# Sheet1.net
KiCad netlist of a schematic drawn in Altium Designer
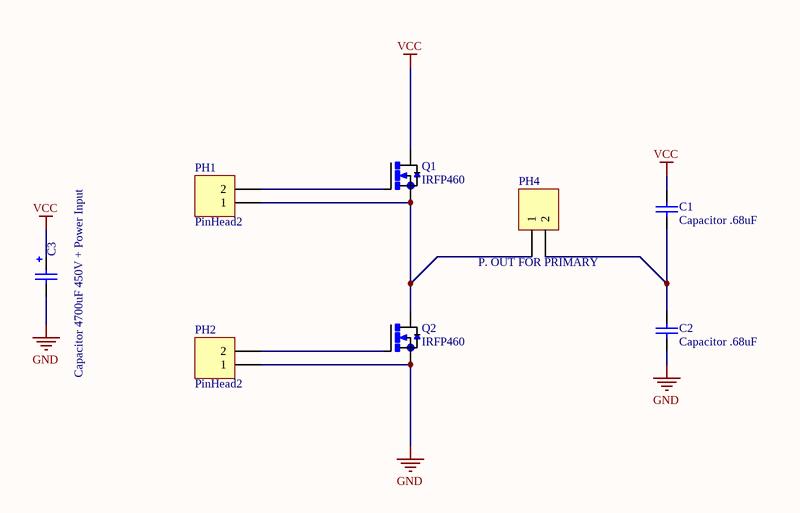
[diagram p0: Sheet1.SchDoc]

(export (version "E")
  (design (tool "Eeschema 10.0.6"))
  (components
    (comp (ref "C1")
      (value "Capacitor .68uF")
      (footprint "Capacitor .68uF")
      (libsource (lib "SPaivachlib1") (part "Capacitor .68uF"))
    )
    (comp (ref "C2")
      (value "Capacitor .68uF")
      (footprint "Capacitor .68uF")
      (libsource (lib "SPaivachlib1") (part "Capacitor .68uF"))
    )
    (comp (ref "C3")
      (value "Capacitor 4700uF 450V + Power Input")
      (footprint "Capacitor 4700uF 450V RIFA")
      (libsource (lib "SPaivachlib1") (part "Capacitor 4700uF 450V"))
    )
    (comp (ref "PH1")
      (value "PinHead2")
      (footprint "PinHead2")
      (libsource (lib "SPaivachlib1") (part "PinHead2"))
    )
    (comp (ref "PH2")
      (value "PinHead2")
      (footprint "PinHead2")
      (libsource (lib "SPaivachlib1") (part "PinHead2"))
    )
    (comp (ref "PH4")
      (value "P. OUT FOR PRIMARY")
      (footprint "P. OUT FOR PRIMARY")
      (libsource (lib "SPaivachlib1") (part "P. OUT FOR PRIMARY"))
    )
    (comp (ref "Q1")
      (value "IRFP460")
      (footprint "IRFP460")
      (libsource (lib "SPaivachlib1") (part "IRFP460"))
    )
    (comp (ref "Q2")
      (value "IRFP460")
      (footprint "IRFP460")
      (libsource (lib "SPaivachlib1") (part "IRFP460"))
    )
  )
  (nets
    (net (code "1") (name "GND") (class "Default")
      (node (ref "C2") (pin "2") (pinfunction "2_2") (pintype "passive"))
      (node (ref "C3") (pin "1") (pinfunction "1_1") (pintype "passive"))
      (node (ref "PH2") (pin "1") (pinfunction "1_1") (pintype "passive"))
      (node (ref "Q2") (pin "S") (pinfunction "S_S") (pintype "passive"))
    )
    (net (code "2") (name "Net-(C1-Pad2)") (class "Default")
      (node (ref "C1") (pin "2") (pinfunction "2_2") (pintype "passive"))
      (node (ref "C2") (pin "1") (pinfunction "1_1") (pintype "passive"))
      (node (ref "PH4") (pin "2") (pinfunction "2_2") (pintype "passive"))
    )
    (net (code "3") (name "Net-(PH1-Pad1)") (class "Default")
      (node (ref "PH1") (pin "1") (pinfunction "1_1") (pintype "passive"))
      (node (ref "PH4") (pin "1") (pinfunction "1_1") (pintype "passive"))
      (node (ref "Q1") (pin "S") (pinfunction "S_S") (pintype "passive"))
      (node (ref "Q2") (pin "D") (pinfunction "D_D") (pintype "passive"))
    )
    (net (code "4") (name "Net-(PH1-Pad2)") (class "Default")
      (node (ref "PH1") (pin "2") (pinfunction "2_2") (pintype "passive"))
      (node (ref "Q1") (pin "G") (pinfunction "G_G") (pintype "passive"))
    )
    (net (code "5") (name "Net-(PH2-Pad2)") (class "Default")
      (node (ref "PH2") (pin "2") (pinfunction "2_2") (pintype "passive"))
      (node (ref "Q2") (pin "G") (pinfunction "G_G") (pintype "passive"))
    )
    (net (code "6") (name "VCC") (class "Default")
      (node (ref "C1") (pin "1") (pinfunction "1_1") (pintype "passive"))
      (node (ref "C3") (pin "2") (pinfunction "2_2") (pintype "passive"))
      (node (ref "Q1") (pin "D") (pinfunction "D_D") (pintype "passive"))
    )
  )
)
